# 3V3_Block.net
KiCad netlist of a schematic drawn in Altium Designer
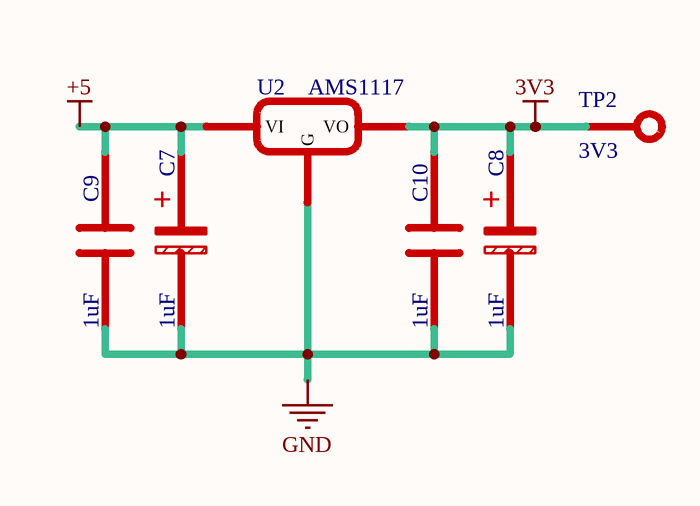
[diagram p0: 3V3_Block.SchDoc]

(export (version "E")
  (design (tool "Eeschema 10.0.6"))
  (components
    (comp (ref "C7")
      (value "1uF")
      (footprint "CAP-AL-4x5.4")
      (description "Aluminum Capacitor")
      (libsource (lib "CTAI-Library") (part "CAP-ALU"))
    )
    (comp (ref "C8")
      (value "1uF")
      (footprint "CAP-AL-4x5.4")
      (description "Aluminum Capacitor")
      (libsource (lib "CTAI-Library") (part "CAP-ALU"))
    )
    (comp (ref "C9")
      (value "1uF")
      (footprint "C0805")
      (description "Ceramic Capacitor")
      (libsource (lib "CTAI-Library") (part "CAP-CER"))
    )
    (comp (ref "C10")
      (value "1uF")
      (footprint "C0805")
      (description "Ceramic Capacitor")
      (libsource (lib "CTAI-Library") (part "CAP-CER"))
    )
    (comp (ref "TP2")
      (value "3V3")
      (footprint "Test Point")
      (description "Test Point")
      (libsource (lib "CTAI-Library") (part "TestPoint"))
    )
    (comp (ref "U2")
      (value "AMS1117")
      (footprint "SOT-223")
      (description "Regulator intergated chip")
      (libsource (lib "CTAI-Library") (part "AMS1117"))
    )
  )
  (nets
    (net (code "1") (name "+5") (class "Default")
      (node (ref "C7") (pin "1") (pintype "passive"))
      (node (ref "C9") (pin "2") (pintype "passive"))
      (node (ref "U2") (pin "3") (pinfunction "VI_3") (pintype "passive"))
    )
    (net (code "2") (name "3V3") (class "Default")
      (node (ref "C10") (pin "2") (pintype "passive"))
      (node (ref "C8") (pin "1") (pintype "passive"))
      (node (ref "TP2") (pin "1") (pinfunction "1_1") (pintype "passive"))
      (node (ref "U2") (pin "2") (pinfunction "VO_2") (pintype "passive"))
    )
    (net (code "3") (name "GND") (class "Default")
      (node (ref "C10") (pin "1") (pintype "passive"))
      (node (ref "C7") (pin "2") (pintype "passive"))
      (node (ref "C8") (pin "2") (pintype "passive"))
      (node (ref "C9") (pin "1") (pintype "passive"))
      (node (ref "U2") (pin "1") (pinfunction "G_1") (pintype "passive"))
    )
  )
)
